# BB-Powersupply_KNX-Connection_-_v1_0_0.net
KiCad netlist of a schematic drawn in EAGLE
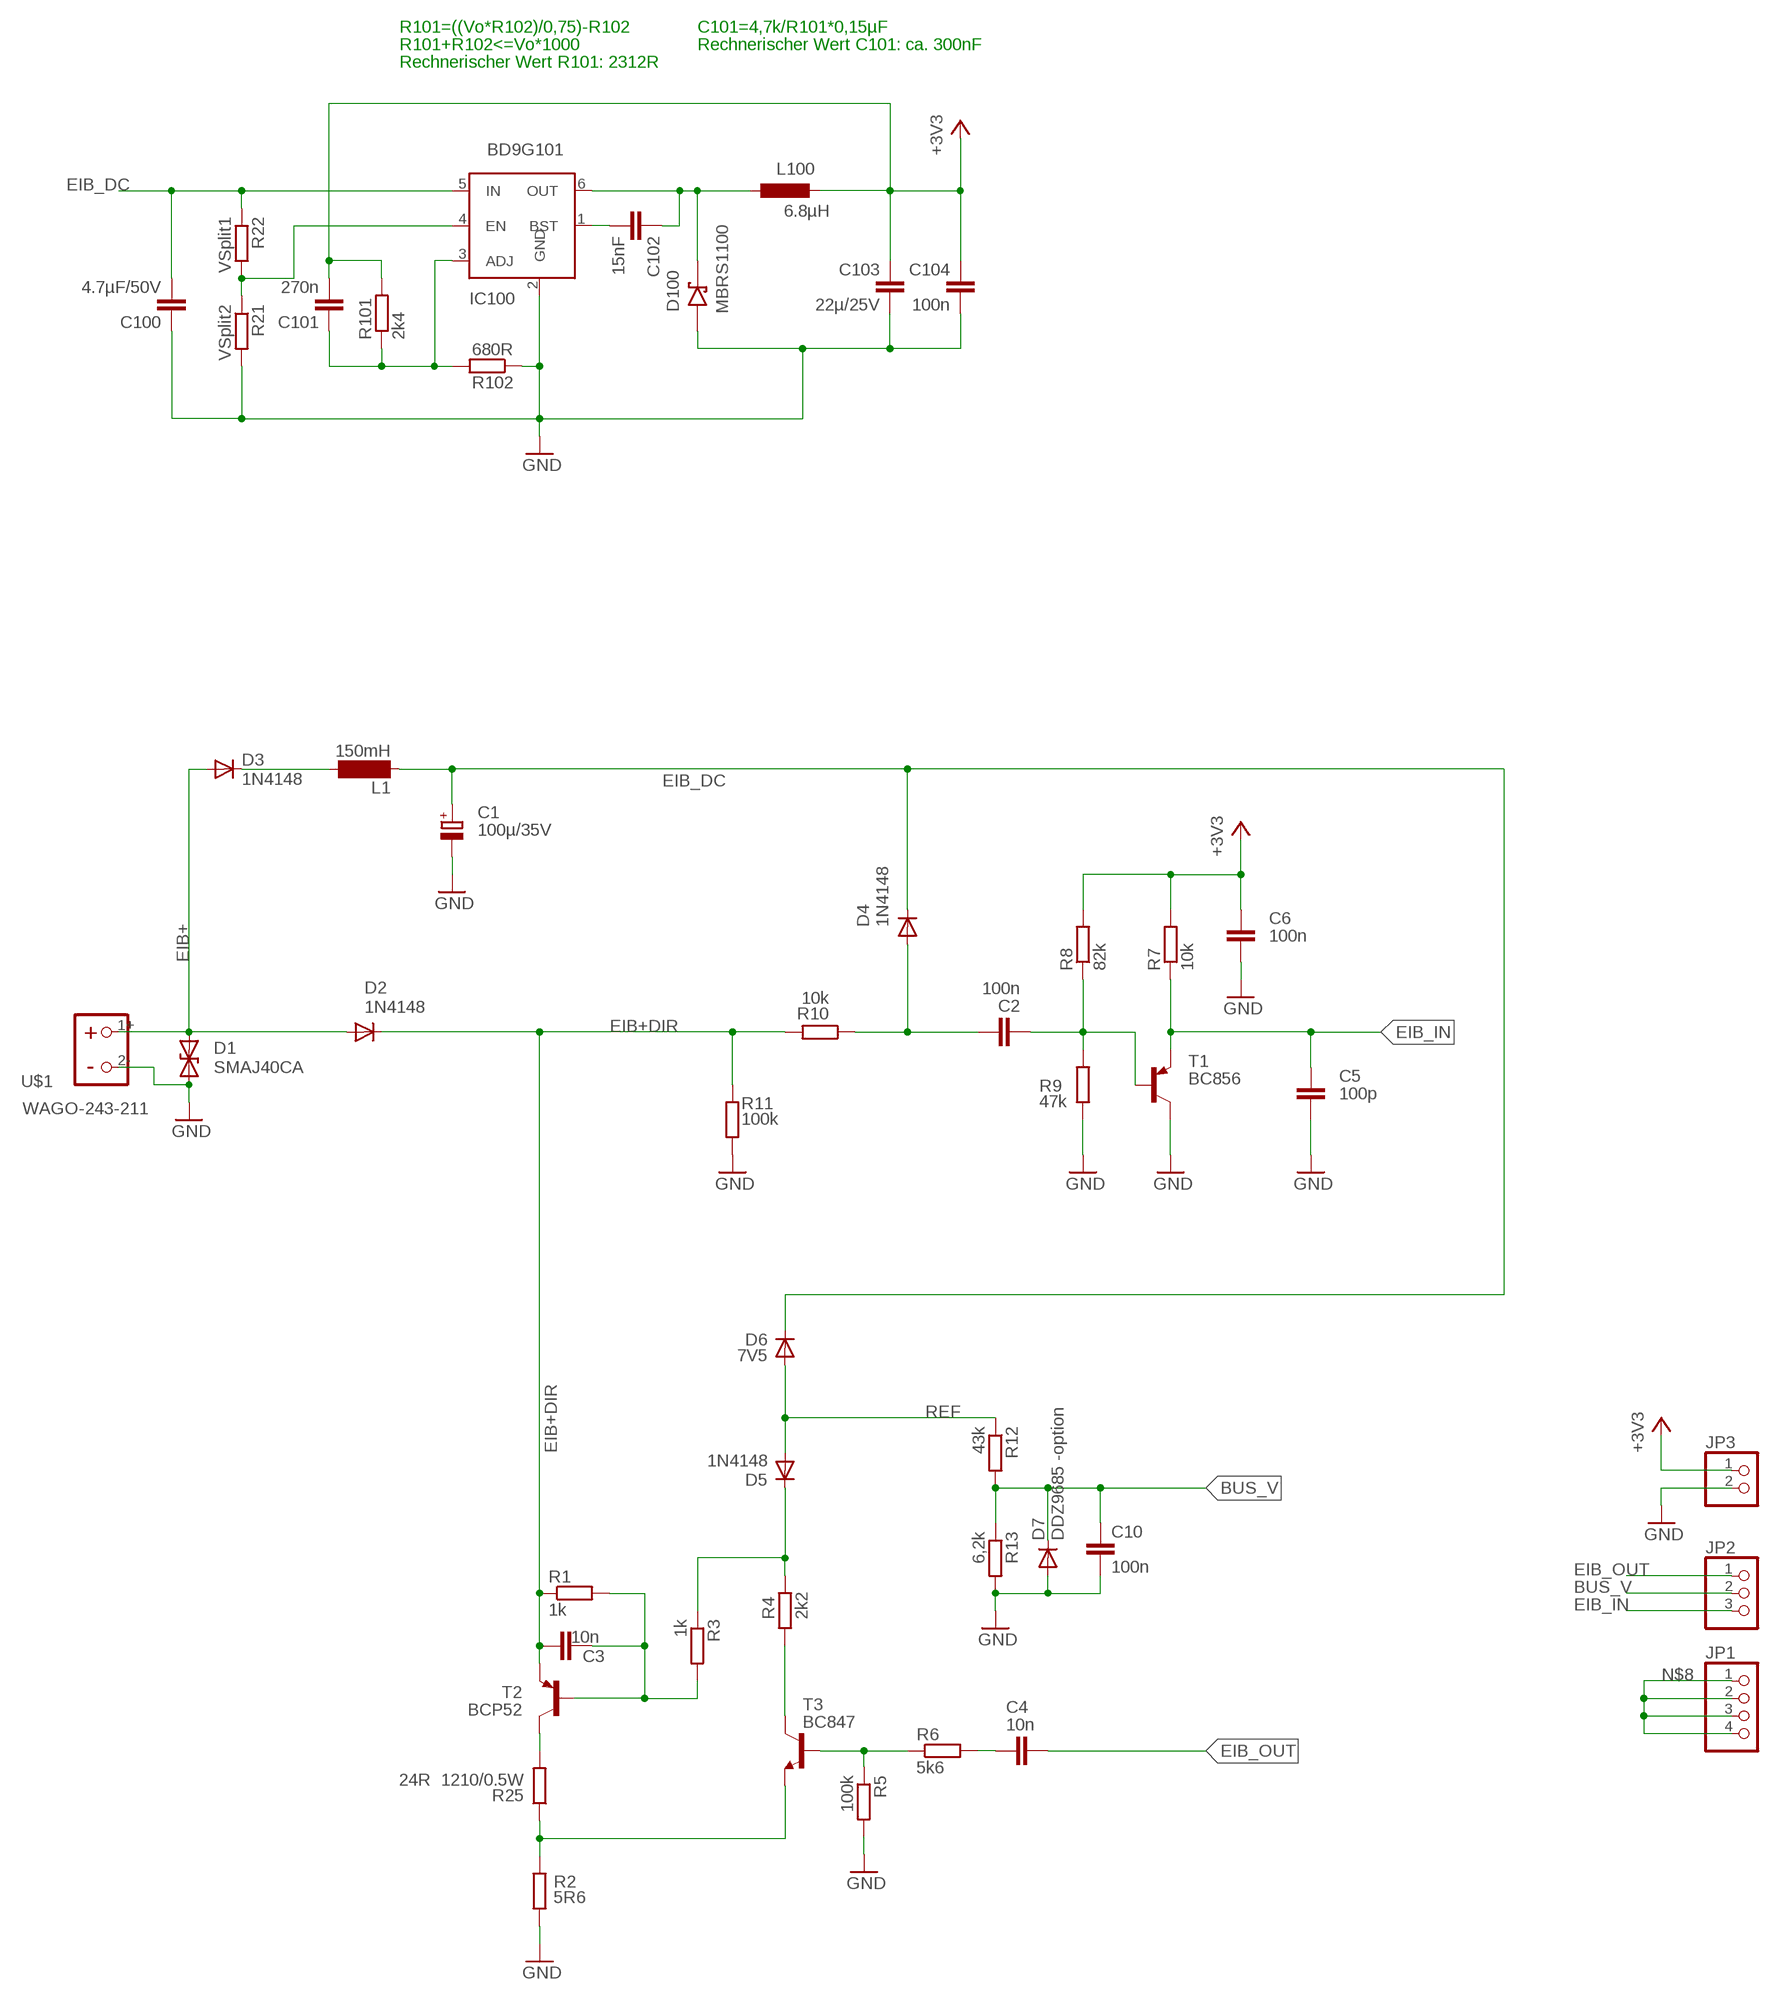
[diagram p0: schematic, sheet 1]

(export (version "E")
  (design (tool "Eeschema 10.0.6"))
  (components
    (comp (ref "C1")
      (value "100µ/35V")
      (footprint "eagle-import:SANYO-OSCON_SMD_C6")
      (libsource (lib "eagle-import") (part "CPOL-EUSANYO_SMD_C6"))
    )
    (comp (ref "C2")
      (value "100n")
      (footprint "eagle-import:C0805")
      (libsource (lib "eagle-import") (part "C-EUC0805"))
    )
    (comp (ref "C3")
      (value "10n")
      (footprint "eagle-import:C0805")
      (libsource (lib "eagle-import") (part "C-EUC0805"))
    )
    (comp (ref "C4")
      (value "10n")
      (footprint "eagle-import:C0805")
      (libsource (lib "eagle-import") (part "C-EUC0805"))
    )
    (comp (ref "C5")
      (value "100p")
      (footprint "eagle-import:C0805")
      (libsource (lib "eagle-import") (part "C-EUC0805"))
    )
    (comp (ref "C6")
      (value "100n")
      (footprint "eagle-import:C0805")
      (libsource (lib "eagle-import") (part "C-EUC0805"))
    )
    (comp (ref "C10")
      (value "100n")
      (footprint "eagle-import:C0805")
      (libsource (lib "eagle-import") (part "C-EUC0805"))
    )
    (comp (ref "C100")
      (value "4.7µF/50V")
      (footprint "eagle-import:C0805")
      (libsource (lib "eagle-import") (part "C-EUC0805"))
    )
    (comp (ref "C101")
      (value "270n")
      (footprint "eagle-import:C0805")
      (libsource (lib "eagle-import") (part "C-EUC0805"))
    )
    (comp (ref "C102")
      (value "15nF")
      (footprint "eagle-import:C0805")
      (libsource (lib "eagle-import") (part "C-EUC0805"))
    )
    (comp (ref "C103")
      (value "22µ/25V")
      (footprint "eagle-import:C1206")
      (libsource (lib "eagle-import") (part "C-EUC1206"))
    )
    (comp (ref "C104")
      (value "100n")
      (footprint "eagle-import:C0805")
      (libsource (lib "eagle-import") (part "C-EUC0805"))
    )
    (comp (ref "D1")
      (value "SMAJ40CA")
      (footprint "eagle-import:DO214AC")
      (fields (field (name "MF") "Littelfuse"))
      (libsource (lib "eagle-import") (part "SMAJCA40"))
    )
    (comp (ref "D2")
      (value "1N4148")
      (footprint "eagle-import:SOD-123")
      (libsource (lib "eagle-import") (part "DIODESOD-123"))
    )
    (comp (ref "D3")
      (value "1N4148")
      (footprint "eagle-import:SOD-123")
      (libsource (lib "eagle-import") (part "DIODESOD-123"))
    )
    (comp (ref "D4")
      (value "1N4148")
      (footprint "eagle-import:SOD-123")
      (libsource (lib "eagle-import") (part "DIODESOD-123"))
    )
    (comp (ref "D5")
      (value "1N4148")
      (footprint "eagle-import:SOD-123")
      (libsource (lib "eagle-import") (part "DIODESOD-123"))
    )
    (comp (ref "D6")
      (value "7V5")
      (footprint "eagle-import:SOD-123")
      (libsource (lib "eagle-import") (part "DIODESOD-123"))
    )
    (comp (ref "D7")
      (value "DDZ9685 -option")
      (footprint "eagle-import:SOD-123")
      (libsource (lib "eagle-import") (part "DIODESOD-123"))
    )
    (comp (ref "D100")
      (value "MBRS1100")
      (footprint "eagle-import:SOD123FL")
      (libsource (lib "eagle-import") (part "SCHOTTKY-DIODE-MBR130LSFT1"))
    )
    (comp (ref "IC100")
      (value "BD9G101")
      (footprint "eagle-import:SOT23-6")
      (libsource (lib "eagle-import") (part "BD9G101GBD9G101G-SOT23-6"))
    )
    (comp (ref "JP1")
      (value "PINHD-1X4")
      (footprint "eagle-import:1X04")
      (libsource (lib "eagle-import") (part "PINHD-1X4"))
    )
    (comp (ref "JP2")
      (value "PINHD-1X3")
      (footprint "eagle-import:1X03")
      (libsource (lib "eagle-import") (part "PINHD-1X3"))
    )
    (comp (ref "JP3")
      (value "PINHD-1X2")
      (footprint "eagle-import:1X02")
      (libsource (lib "eagle-import") (part "PINHD-1X2"))
    )
    (comp (ref "L1")
      (value "150mH")
      (footprint "eagle-import:BS11")
      (fields (field (name "SPICEPREFIX") "L"))
      (libsource (lib "eagle-import") (part "BS11"))
    )
    (comp (ref "L100")
      (value "6.8µH")
      (footprint "eagle-import:L4532P")
      (libsource (lib "eagle-import") (part "L-EUL4532P"))
    )
    (comp (ref "R1")
      (value "1k")
      (footprint "eagle-import:R0805")
      (libsource (lib "eagle-import") (part "R-EU_R0805"))
    )
    (comp (ref "R2")
      (value "5R6")
      (footprint "eagle-import:R0805")
      (libsource (lib "eagle-import") (part "R-EU_R0805"))
    )
    (comp (ref "R3")
      (value "1k")
      (footprint "eagle-import:R0805")
      (libsource (lib "eagle-import") (part "R-EU_R0805"))
    )
    (comp (ref "R4")
      (value "2k2")
      (footprint "eagle-import:R0805")
      (libsource (lib "eagle-import") (part "R-EU_R0805"))
    )
    (comp (ref "R5")
      (value "100k")
      (footprint "eagle-import:R0805")
      (libsource (lib "eagle-import") (part "R-EU_R0805"))
    )
    (comp (ref "R6")
      (value "5k6")
      (footprint "eagle-import:R0805")
      (libsource (lib "eagle-import") (part "R-EU_R0805"))
    )
    (comp (ref "R7")
      (value "10k")
      (footprint "eagle-import:R0805")
      (libsource (lib "eagle-import") (part "R-EU_R0805"))
    )
    (comp (ref "R8")
      (value "82k")
      (footprint "eagle-import:R0805")
      (libsource (lib "eagle-import") (part "R-EU_R0805"))
    )
    (comp (ref "R9")
      (value "47k")
      (footprint "eagle-import:R0805")
      (libsource (lib "eagle-import") (part "R-EU_R0805"))
    )
    (comp (ref "R10")
      (value "10k")
      (footprint "eagle-import:R0805")
      (libsource (lib "eagle-import") (part "R-EU_R0805"))
    )
    (comp (ref "R11")
      (value "100k")
      (footprint "eagle-import:R0805")
      (libsource (lib "eagle-import") (part "R-EU_R0805"))
    )
    (comp (ref "R12")
      (value "43k")
      (footprint "eagle-import:R0805")
      (libsource (lib "eagle-import") (part "R-EU_R0805"))
    )
    (comp (ref "R13")
      (value "6,2k")
      (footprint "eagle-import:R0805")
      (libsource (lib "eagle-import") (part "R-EU_R0805"))
    )
    (comp (ref "R21")
      (value "VSplit2")
      (footprint "eagle-import:R0805")
      (libsource (lib "eagle-import") (part "R-EU_R0805"))
    )
    (comp (ref "R22")
      (value "VSplit1")
      (footprint "eagle-import:R0805")
      (libsource (lib "eagle-import") (part "R-EU_R0805"))
    )
    (comp (ref "R25")
      (value "24R 1210/0.5W")
      (footprint "eagle-import:R2512")
      (libsource (lib "eagle-import") (part "R-EU_R2512"))
    )
    (comp (ref "R101")
      (value "2k4")
      (footprint "eagle-import:R0805")
      (libsource (lib "eagle-import") (part "R-EU_R0805"))
    )
    (comp (ref "R102")
      (value "680R")
      (footprint "eagle-import:R0805")
      (libsource (lib "eagle-import") (part "R-EU_R0805"))
    )
    (comp (ref "T1")
      (value "BC856")
      (footprint "eagle-import:SOT23-BEC")
      (libsource (lib "eagle-import") (part "BC856SMDB"))
    )
    (comp (ref "T2")
      (value "BCP52")
      (footprint "eagle-import:SOT223")
      (libsource (lib "eagle-import") (part "FZT753SMD"))
    )
    (comp (ref "T3")
      (value "BC847")
      (footprint "eagle-import:SOT23")
      (libsource (lib "eagle-import") (part "BC847"))
    )
    (comp (ref "U$1")
      (value "WAGO-243-211")
      (footprint "eagle-import:WAGO-243-211")
      (libsource (lib "eagle-import") (part "WAGO-243-211"))
    )
  )
  (nets
    (net (code "1") (name "+3V3") (class "Default")
      (node (ref "C101") (pin "2") (pinfunction "2_2") (pintype "passive"))
      (node (ref "C103") (pin "1") (pinfunction "1_1") (pintype "passive"))
      (node (ref "C104") (pin "1") (pinfunction "1_1") (pintype "passive"))
      (node (ref "C6") (pin "2") (pinfunction "2_2") (pintype "passive"))
      (node (ref "JP3") (pin "1") (pinfunction "1_1") (pintype "passive"))
      (node (ref "L100") (pin "2") (pinfunction "2_2") (pintype "passive"))
      (node (ref "R101") (pin "2") (pinfunction "2_2") (pintype "passive"))
      (node (ref "R7") (pin "2") (pinfunction "2_2") (pintype "passive"))
      (node (ref "R8") (pin "2") (pinfunction "2_2") (pintype "passive"))
    )
    (net (code "2") (name "/EIB+") (class "Default")
      (node (ref "D1") (pin "C") (pinfunction "2_C") (pintype "passive"))
      (node (ref "D2") (pin "A") (pinfunction "A_A") (pintype "passive"))
      (node (ref "D3") (pin "A") (pinfunction "A_A") (pintype "passive"))
      (node (ref "U$1") (pin "1+") (pinfunction "1+_1+") (pintype "passive"))
    )
    (net (code "3") (name "/EIB+DIR") (class "Default")
      (node (ref "C3") (pin "1") (pinfunction "1_1") (pintype "passive"))
      (node (ref "D2") (pin "C") (pinfunction "C_C") (pintype "passive"))
      (node (ref "R1") (pin "1") (pinfunction "1_1") (pintype "passive"))
      (node (ref "R10") (pin "2") (pinfunction "2_2") (pintype "passive"))
      (node (ref "R11") (pin "2") (pinfunction "2_2") (pintype "passive"))
      (node (ref "T2") (pin "3") (pinfunction "E_3") (pintype "passive"))
    )
    (net (code "4") (name "/EIB_DC") (class "Default")
      (node (ref "C1") (pin "+") (pinfunction "+_+") (pintype "passive"))
      (node (ref "C100") (pin "2") (pinfunction "2_2") (pintype "passive"))
      (node (ref "D4") (pin "C") (pinfunction "C_C") (pintype "passive"))
      (node (ref "D6") (pin "C") (pinfunction "C_C") (pintype "passive"))
      (node (ref "IC100") (pin "5") (pinfunction "IN_5") (pintype "input"))
      (node (ref "L1") (pin "1") (pinfunction "1_1") (pintype "passive"))
      (node (ref "R22") (pin "1") (pinfunction "1_1") (pintype "passive"))
    )
    (net (code "5") (name "/N$8") (class "Default")
      (node (ref "JP1") (pin "1") (pinfunction "1_1") (pintype "passive"))
      (node (ref "JP1") (pin "2") (pinfunction "2_2") (pintype "passive"))
      (node (ref "JP1") (pin "3") (pinfunction "3_3") (pintype "passive"))
      (node (ref "JP1") (pin "4") (pinfunction "4_4") (pintype "passive"))
      (node (ref "R25") (pin "2") (pinfunction "2_2") (pintype "passive"))
      (node (ref "T2") (pin "2") (pinfunction "C_2") (pintype "passive"))
      (node (ref "T2") (pin "4") (pinfunction "C_4") (pintype "passive"))
    )
    (net (code "6") (name "/REF") (class "Default")
      (node (ref "D5") (pin "A") (pinfunction "A_A") (pintype "passive"))
      (node (ref "D6") (pin "A") (pinfunction "A_A") (pintype "passive"))
      (node (ref "R12") (pin "1") (pinfunction "1_1") (pintype "passive"))
    )
    (net (code "7") (name "BUS_V") (class "Default")
      (node (ref "C10") (pin "2") (pinfunction "2_2") (pintype "passive"))
      (node (ref "D7") (pin "C") (pinfunction "C_C") (pintype "passive"))
      (node (ref "JP2") (pin "2") (pinfunction "2_2") (pintype "passive"))
      (node (ref "R12") (pin "2") (pinfunction "2_2") (pintype "passive"))
      (node (ref "R13") (pin "1") (pinfunction "1_1") (pintype "passive"))
    )
    (net (code "8") (name "EIB_IN") (class "Default")
      (node (ref "C5") (pin "2") (pinfunction "2_2") (pintype "passive"))
      (node (ref "JP2") (pin "3") (pinfunction "3_3") (pintype "passive"))
      (node (ref "R7") (pin "1") (pinfunction "1_1") (pintype "passive"))
      (node (ref "T1") (pin "E") (pinfunction "E_E") (pintype "passive"))
    )
    (net (code "9") (name "EIB_OUT") (class "Default")
      (node (ref "C4") (pin "2") (pinfunction "2_2") (pintype "passive"))
      (node (ref "JP2") (pin "1") (pinfunction "1_1") (pintype "passive"))
    )
    (net (code "10") (name "GND") (class "Default")
      (node (ref "C1") (pin "-") (pinfunction "-_-") (pintype "passive"))
      (node (ref "C10") (pin "1") (pinfunction "1_1") (pintype "passive"))
      (node (ref "C100") (pin "1") (pinfunction "1_1") (pintype "passive"))
      (node (ref "C103") (pin "2") (pinfunction "2_2") (pintype "passive"))
      (node (ref "C104") (pin "2") (pinfunction "2_2") (pintype "passive"))
      (node (ref "C5") (pin "1") (pinfunction "1_1") (pintype "passive"))
      (node (ref "C6") (pin "1") (pinfunction "1_1") (pintype "passive"))
      (node (ref "D1") (pin "A") (pinfunction "1_A") (pintype "passive"))
      (node (ref "D100") (pin "A") (pinfunction "A_A") (pintype "passive"))
      (node (ref "D7") (pin "A") (pinfunction "A_A") (pintype "passive"))
      (node (ref "IC100") (pin "2") (pinfunction "GND_2") (pintype "power_in"))
      (node (ref "JP3") (pin "2") (pinfunction "2_2") (pintype "passive"))
      (node (ref "R102") (pin "1") (pinfunction "1_1") (pintype "passive"))
      (node (ref "R11") (pin "1") (pinfunction "1_1") (pintype "passive"))
      (node (ref "R13") (pin "2") (pinfunction "2_2") (pintype "passive"))
      (node (ref "R2") (pin "1") (pinfunction "1_1") (pintype "passive"))
      (node (ref "R21") (pin "2") (pinfunction "2_2") (pintype "passive"))
      (node (ref "R5") (pin "2") (pinfunction "2_2") (pintype "passive"))
      (node (ref "R9") (pin "1") (pinfunction "1_1") (pintype "passive"))
      (node (ref "T1") (pin "C") (pinfunction "C_C") (pintype "passive"))
      (node (ref "U$1") (pin "2-") (pinfunction "2-_2-") (pintype "passive"))
    )
    (net (code "11") (name "Net-(C2-Pad1)") (class "Default")
      (node (ref "C2") (pin "1") (pinfunction "1_1") (pintype "passive"))
      (node (ref "R8") (pin "1") (pinfunction "1_1") (pintype "passive"))
      (node (ref "R9") (pin "2") (pinfunction "2_2") (pintype "passive"))
      (node (ref "T1") (pin "B") (pinfunction "B_B") (pintype "passive"))
    )
    (net (code "12") (name "Net-(C2-Pad2)") (class "Default")
      (node (ref "C2") (pin "2") (pinfunction "2_2") (pintype "passive"))
      (node (ref "D4") (pin "A") (pinfunction "A_A") (pintype "passive"))
      (node (ref "R10") (pin "1") (pinfunction "1_1") (pintype "passive"))
    )
    (net (code "13") (name "Net-(C4-Pad1)") (class "Default")
      (node (ref "C4") (pin "1") (pinfunction "1_1") (pintype "passive"))
      (node (ref "R6") (pin "2") (pinfunction "2_2") (pintype "passive"))
    )
    (net (code "14") (name "Net-(D3-PadC)") (class "Default")
      (node (ref "D3") (pin "C") (pinfunction "C_C") (pintype "passive"))
      (node (ref "L1") (pin "2") (pinfunction "2_2") (pintype "passive"))
    )
    (net (code "15") (name "Net-(D5-PadC)") (class "Default")
      (node (ref "D5") (pin "C") (pinfunction "C_C") (pintype "passive"))
      (node (ref "R3") (pin "1") (pinfunction "1_1") (pintype "passive"))
      (node (ref "R4") (pin "2") (pinfunction "2_2") (pintype "passive"))
    )
    (net (code "16") (name "Net-(IC100-ADJ)") (class "Default")
      (node (ref "C101") (pin "1") (pinfunction "1_1") (pintype "passive"))
      (node (ref "IC100") (pin "3") (pinfunction "ADJ_3") (pintype "passive"))
      (node (ref "R101") (pin "1") (pinfunction "1_1") (pintype "passive"))
      (node (ref "R102") (pin "2") (pinfunction "2_2") (pintype "passive"))
    )
    (net (code "17") (name "Net-(IC100-BST)") (class "Default")
      (node (ref "C102") (pin "2") (pinfunction "2_2") (pintype "passive"))
      (node (ref "IC100") (pin "1") (pinfunction "BST_1") (pintype "output"))
    )
    (net (code "18") (name "Net-(IC100-EN)") (class "Default")
      (node (ref "IC100") (pin "4") (pinfunction "EN_4") (pintype "input"))
      (node (ref "R21") (pin "1") (pinfunction "1_1") (pintype "passive"))
      (node (ref "R22") (pin "2") (pinfunction "2_2") (pintype "passive"))
    )
    (net (code "19") (name "Net-(IC100-OUT)") (class "Default")
      (node (ref "C102") (pin "1") (pinfunction "1_1") (pintype "passive"))
      (node (ref "D100") (pin "C") (pinfunction "C_C") (pintype "passive"))
      (node (ref "IC100") (pin "6") (pinfunction "OUT_6") (pintype "output"))
      (node (ref "L100") (pin "1") (pinfunction "1_1") (pintype "passive"))
    )
    (net (code "20") (name "Net-(T2-B)") (class "Default")
      (node (ref "C3") (pin "2") (pinfunction "2_2") (pintype "passive"))
      (node (ref "R1") (pin "2") (pinfunction "2_2") (pintype "passive"))
      (node (ref "R3") (pin "2") (pinfunction "2_2") (pintype "passive"))
      (node (ref "T2") (pin "1") (pinfunction "B_1") (pintype "passive"))
    )
    (net (code "21") (name "Net-(T3-B)") (class "Default")
      (node (ref "R5") (pin "1") (pinfunction "1_1") (pintype "passive"))
      (node (ref "R6") (pin "1") (pinfunction "1_1") (pintype "passive"))
      (node (ref "T3") (pin "1") (pinfunction "B_1") (pintype "passive"))
    )
    (net (code "22") (name "Net-(T3-C)") (class "Default")
      (node (ref "R4") (pin "1") (pinfunction "1_1") (pintype "passive"))
      (node (ref "T3") (pin "3") (pinfunction "C_3") (pintype "passive"))
    )
    (net (code "23") (name "Net-(T3-E)") (class "Default")
      (node (ref "R2") (pin "2") (pinfunction "2_2") (pintype "passive"))
      (node (ref "R25") (pin "1") (pinfunction "1_1") (pintype "passive"))
      (node (ref "T3") (pin "2") (pinfunction "E_2") (pintype "passive"))
    )
  )
)
